# RocMan.net
KiCad netlist of a schematic drawn in EAGLE
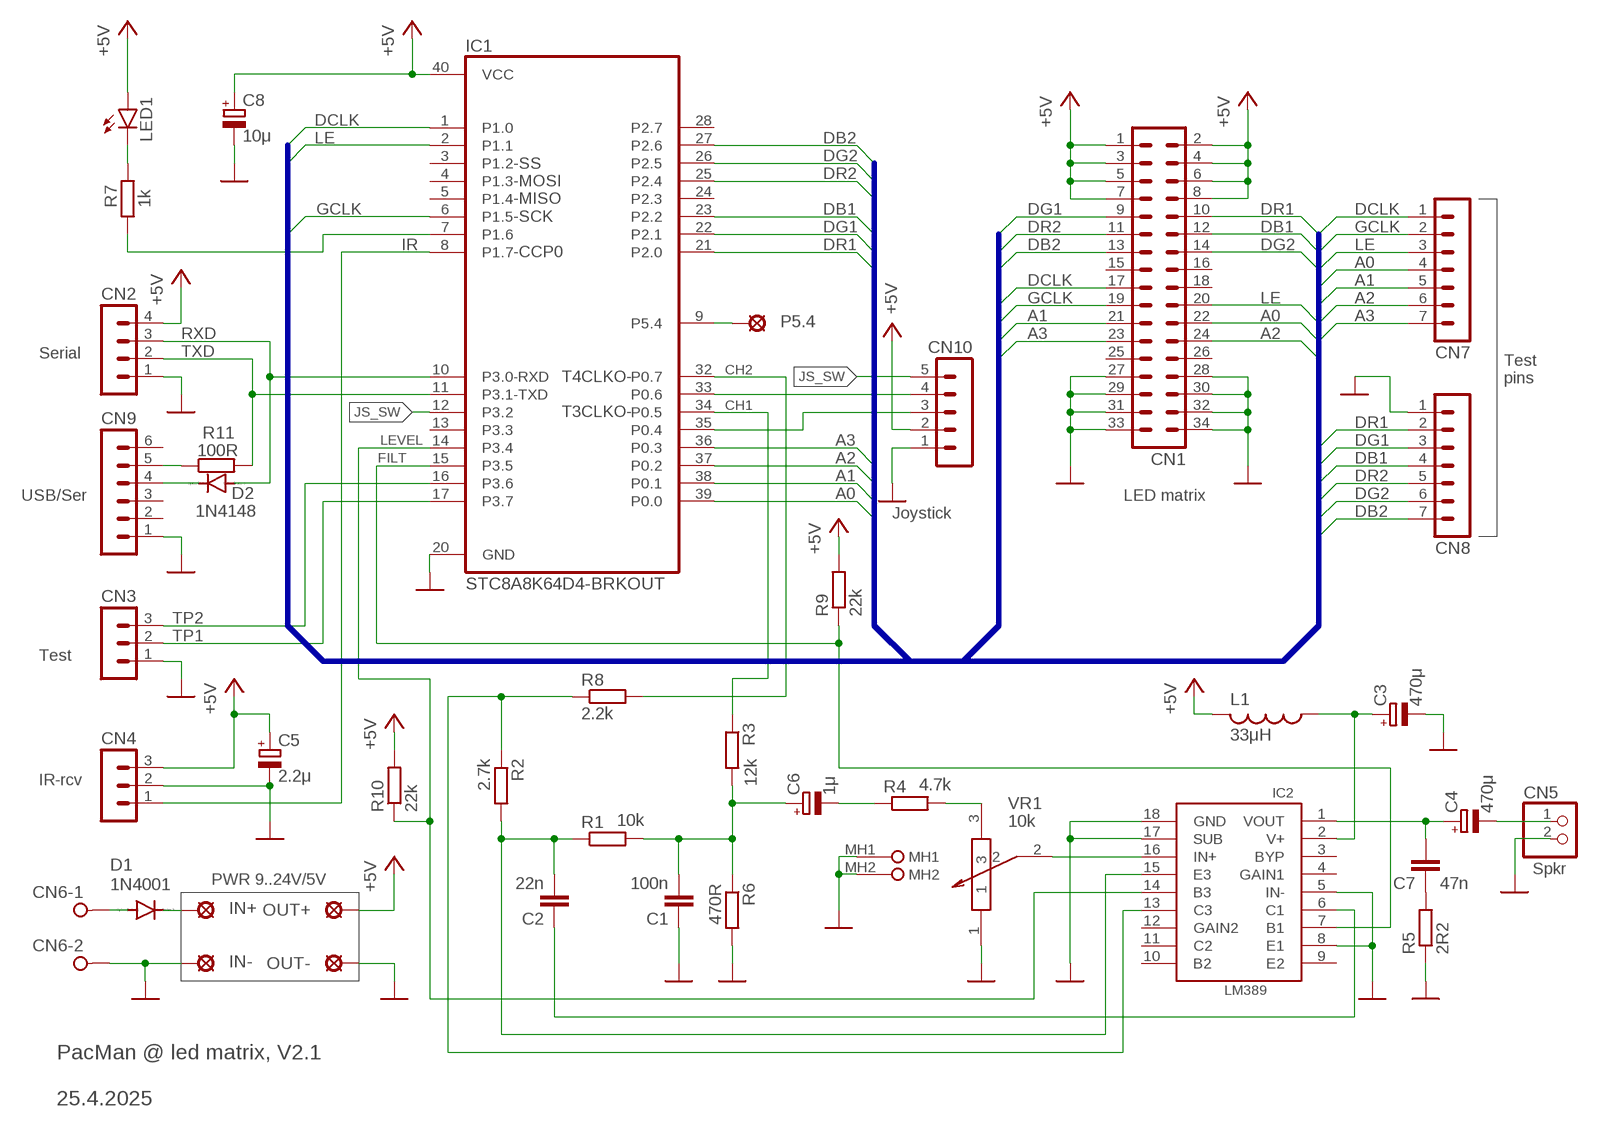
[diagram p0: schematic, sheet 1]

(export (version "E")
  (design (tool "Eeschema 10.0.6"))
  (components
    (comp (ref "C1")
      (value "100n")
      (footprint "eagle-import:C0805")
      (libsource (lib "eagle-import") (part "C-EUC0805"))
    )
    (comp (ref "C2")
      (value "22n")
      (footprint "eagle-import:C0805")
      (libsource (lib "eagle-import") (part "C-EUC0805"))
    )
    (comp (ref "C3")
      (value "470μ")
      (footprint "eagle-import:E5-10,5")
      (libsource (lib "eagle-import") (part "CPOL-EUE5-10.5"))
    )
    (comp (ref "C4")
      (value "470μ")
      (footprint "eagle-import:E5-10,5")
      (libsource (lib "eagle-import") (part "CPOL-EUE5-10.5"))
    )
    (comp (ref "C5")
      (value "2.2μ")
      (footprint "eagle-import:SMC_A")
      (libsource (lib "eagle-import") (part "CPOL-EUSMCA"))
    )
    (comp (ref "C6")
      (value "1μ")
      (footprint "eagle-import:SMC_A")
      (libsource (lib "eagle-import") (part "CPOL-EUSMCA"))
    )
    (comp (ref "C7")
      (value "47n")
      (footprint "eagle-import:C0805")
      (libsource (lib "eagle-import") (part "C-EUC0805"))
    )
    (comp (ref "C8")
      (value "10μ")
      (footprint "eagle-import:SMC_A")
      (libsource (lib "eagle-import") (part "CPOL-EUSMCA"))
    )
    (comp (ref "CN1")
      (value "ML34")
      (footprint "eagle-import:ML34")
      (libsource (lib "eagle-import") (part "ML34"))
    )
    (comp (ref "CN2")
      (value "MA04-1")
      (footprint "eagle-import:MA04-1")
      (libsource (lib "eagle-import") (part "MA04-1"))
    )
    (comp (ref "CN3")
      (value "MA03-1")
      (footprint "eagle-import:MA03-1")
      (libsource (lib "eagle-import") (part "MA03-1"))
    )
    (comp (ref "CN4")
      (value "MA03-1")
      (footprint "eagle-import:MA03-1")
      (libsource (lib "eagle-import") (part "MA03-1"))
    )
    (comp (ref "CN5")
      (value "PINHD-1X2")
      (footprint "eagle-import:1X02")
      (libsource (lib "eagle-import") (part "PINHD-1X2"))
    )
    (comp (ref "CN6")
      (value "W237-02P")
      (footprint "eagle-import:W237-132")
      (libsource (lib "eagle-import") (part "W237-02P"))
    )
    (comp (ref "CN7")
      (value "MA07-1")
      (footprint "eagle-import:MA07-1")
      (libsource (lib "eagle-import") (part "MA07-1"))
    )
    (comp (ref "CN8")
      (value "MA07-1")
      (footprint "eagle-import:MA07-1")
      (libsource (lib "eagle-import") (part "MA07-1"))
    )
    (comp (ref "CN9")
      (value "MA06-1")
      (footprint "eagle-import:MA06-1")
      (libsource (lib "eagle-import") (part "MA06-1"))
    )
    (comp (ref "CN10")
      (value "MA05-1")
      (footprint "eagle-import:MA05-1")
      (libsource (lib "eagle-import") (part "MA05-1"))
    )
    (comp (ref "D1")
      (value "1N4001")
      (footprint "eagle-import:DO41-10")
      (libsource (lib "eagle-import") (part "1N4004"))
    )
    (comp (ref "D2")
      (value "1N4148")
      (footprint "eagle-import:SOD123")
      (libsource (lib "eagle-import") (part "DIODE-SOD123"))
    )
    (comp (ref "IC1")
      (value "STC8A8K64D4-BRKOUT")
      (footprint "eagle-import:DIL40")
      (libsource (lib "eagle-import") (part "STC8A8K64D4-BRKOUT"))
    )
    (comp (ref "IC2")
      (value "LM389")
      (footprint "eagle-import:DIL18")
      (libsource (lib "eagle-import") (part "LM389"))
    )
    (comp (ref "IN+")
      (value "LSP11")
      (footprint "eagle-import:LSP11")
      (libsource (lib "eagle-import") (part "LSP11"))
    )
    (comp (ref "IN-")
      (value "LSP11")
      (footprint "eagle-import:LSP11")
      (libsource (lib "eagle-import") (part "LSP11"))
    )
    (comp (ref "L1")
      (value "33μH")
      (footprint "eagle-import:L4532M")
      (libsource (lib "eagle-import") (part "L-USL4532C"))
    )
    (comp (ref "LED1")
      (value "LEDCHIP-LED0805")
      (footprint "eagle-import:CHIP-LED0805")
      (libsource (lib "eagle-import") (part "LEDCHIP-LED0805"))
    )
    (comp (ref "OUT+")
      (value "LSP11")
      (footprint "eagle-import:LSP11")
      (libsource (lib "eagle-import") (part "LSP11"))
    )
    (comp (ref "OUT-")
      (value "LSP11")
      (footprint "eagle-import:LSP11")
      (libsource (lib "eagle-import") (part "LSP11"))
    )
    (comp (ref "P5.4")
      (value "LSP11")
      (footprint "eagle-import:LSP11")
      (libsource (lib "eagle-import") (part "LSP11"))
    )
    (comp (ref "R1")
      (value "10k")
      (footprint "eagle-import:R0805")
      (libsource (lib "eagle-import") (part "R-EU_R0805"))
    )
    (comp (ref "R2")
      (value "2.7k")
      (footprint "eagle-import:R0805")
      (libsource (lib "eagle-import") (part "R-EU_R0805"))
    )
    (comp (ref "R3")
      (value "12k")
      (footprint "eagle-import:R0805")
      (libsource (lib "eagle-import") (part "R-EU_R0805"))
    )
    (comp (ref "R4")
      (value "4.7k")
      (footprint "eagle-import:R0805")
      (libsource (lib "eagle-import") (part "R-EU_R0805"))
    )
    (comp (ref "R5")
      (value "2R2")
      (footprint "eagle-import:R0805")
      (libsource (lib "eagle-import") (part "R-EU_R0805"))
    )
    (comp (ref "R6")
      (value "470R")
      (footprint "eagle-import:R0805")
      (libsource (lib "eagle-import") (part "R-EU_R0805"))
    )
    (comp (ref "R7")
      (value "1k")
      (footprint "eagle-import:R0805")
      (libsource (lib "eagle-import") (part "R-EU_R0805"))
    )
    (comp (ref "R8")
      (value "2.2k")
      (footprint "eagle-import:R0805")
      (libsource (lib "eagle-import") (part "R-EU_R0805"))
    )
    (comp (ref "R9")
      (value "22k")
      (footprint "eagle-import:R0805")
      (libsource (lib "eagle-import") (part "R-EU_R0805"))
    )
    (comp (ref "R10")
      (value "22k")
      (footprint "eagle-import:R0805")
      (libsource (lib "eagle-import") (part "R-EU_R0805"))
    )
    (comp (ref "R11")
      (value "100R")
      (footprint "eagle-import:R0805")
      (libsource (lib "eagle-import") (part "R-EU_R0805"))
    )
    (comp (ref "VR1")
      (value "10k")
      (footprint "eagle-import:PTV09A4015FA103")
      (fields
        (field (name "MANUFACTURER_PART_NUMBER") "PTV09A-4015F-A103")
        (field (name "MOUSER_PART_NUMBER") "652-PTV09A-4015FA103")
      )
      (libsource (lib "eagle-import") (part "PTV09A-4015F-A103"))
    )
  )
  (nets
    (net (code "1") (name "+5V") (class "Default")
      (node (ref "C5") (pin "+") (pinfunction "+_+") (pintype "passive"))
      (node (ref "C8") (pin "+") (pinfunction "+_+") (pintype "passive"))
      (node (ref "CN1") (pin "1") (pinfunction "1_1") (pintype "passive"))
      (node (ref "CN1") (pin "2") (pinfunction "2_2") (pintype "passive"))
      (node (ref "CN1") (pin "3") (pinfunction "3_3") (pintype "passive"))
      (node (ref "CN1") (pin "4") (pinfunction "4_4") (pintype "passive"))
      (node (ref "CN1") (pin "5") (pinfunction "5_5") (pintype "passive"))
      (node (ref "CN1") (pin "6") (pinfunction "6_6") (pintype "passive"))
      (node (ref "CN1") (pin "7") (pinfunction "7_7") (pintype "passive"))
      (node (ref "CN1") (pin "8") (pinfunction "8_8") (pintype "passive"))
      (node (ref "CN10") (pin "2") (pinfunction "2_2") (pintype "passive"))
      (node (ref "CN2") (pin "4") (pinfunction "4_4") (pintype "passive"))
      (node (ref "CN4") (pin "3") (pinfunction "3_3") (pintype "passive"))
      (node (ref "IC1") (pin "40") (pinfunction "VCC_40") (pintype "power_in"))
      (node (ref "L1") (pin "2") (pinfunction "2_2") (pintype "passive"))
      (node (ref "LED1") (pin "A") (pinfunction "A_A") (pintype "passive"))
      (node (ref "OUT+") (pin "MP") (pinfunction "MP_MP") (pintype "passive"))
      (node (ref "R10") (pin "2") (pinfunction "2_2") (pintype "passive"))
      (node (ref "R9") (pin "2") (pinfunction "2_2") (pintype "passive"))
    )
    (net (code "2") (name "/A0") (class "Default")
      (node (ref "CN1") (pin "22") (pinfunction "22_22") (pintype "passive"))
      (node (ref "CN7") (pin "4") (pinfunction "4_4") (pintype "passive"))
      (node (ref "IC1") (pin "39") (pinfunction "P0.0_39") (pintype "bidirectional"))
    )
    (net (code "3") (name "/A1") (class "Default")
      (node (ref "CN1") (pin "21") (pinfunction "21_21") (pintype "passive"))
      (node (ref "CN7") (pin "5") (pinfunction "5_5") (pintype "passive"))
      (node (ref "IC1") (pin "38") (pinfunction "P0.1_38") (pintype "bidirectional"))
    )
    (net (code "4") (name "/A2") (class "Default")
      (node (ref "CN1") (pin "24") (pinfunction "24_24") (pintype "passive"))
      (node (ref "CN7") (pin "6") (pinfunction "6_6") (pintype "passive"))
      (node (ref "IC1") (pin "37") (pinfunction "P0.2_37") (pintype "bidirectional"))
    )
    (net (code "5") (name "/A3") (class "Default")
      (node (ref "CN1") (pin "23") (pinfunction "23_23") (pintype "passive"))
      (node (ref "CN7") (pin "7") (pinfunction "7_7") (pintype "passive"))
      (node (ref "IC1") (pin "36") (pinfunction "P0.3_36") (pintype "bidirectional"))
    )
    (net (code "6") (name "/CH1") (class "Default")
      (node (ref "IC1") (pin "34") (pinfunction "P0.5_34") (pintype "bidirectional"))
      (node (ref "R3") (pin "1") (pinfunction "1_1") (pintype "passive"))
    )
    (net (code "7") (name "/CH2") (class "Default")
      (node (ref "IC1") (pin "32") (pinfunction "P0.7_32") (pintype "bidirectional"))
      (node (ref "R8") (pin "2") (pinfunction "2_2") (pintype "passive"))
    )
    (net (code "8") (name "/DB1") (class "Default")
      (node (ref "CN1") (pin "12") (pinfunction "12_12") (pintype "passive"))
      (node (ref "CN8") (pin "4") (pinfunction "4_4") (pintype "passive"))
      (node (ref "IC1") (pin "23") (pinfunction "P2.2_23") (pintype "bidirectional"))
    )
    (net (code "9") (name "/DB2") (class "Default")
      (node (ref "CN1") (pin "13") (pinfunction "13_13") (pintype "passive"))
      (node (ref "CN8") (pin "7") (pinfunction "7_7") (pintype "passive"))
      (node (ref "IC1") (pin "27") (pinfunction "P2.6_27") (pintype "bidirectional"))
    )
    (net (code "10") (name "/DCLK") (class "Default")
      (node (ref "CN1") (pin "17") (pinfunction "17_17") (pintype "passive"))
      (node (ref "CN7") (pin "1") (pinfunction "1_1") (pintype "passive"))
      (node (ref "IC1") (pin "1") (pinfunction "P1.0_1") (pintype "bidirectional"))
    )
    (net (code "11") (name "/DG1") (class "Default")
      (node (ref "CN1") (pin "9") (pinfunction "9_9") (pintype "passive"))
      (node (ref "CN8") (pin "3") (pinfunction "3_3") (pintype "passive"))
      (node (ref "IC1") (pin "22") (pinfunction "P2.1_22") (pintype "bidirectional"))
    )
    (net (code "12") (name "/DG2") (class "Default")
      (node (ref "CN1") (pin "14") (pinfunction "14_14") (pintype "passive"))
      (node (ref "CN8") (pin "6") (pinfunction "6_6") (pintype "passive"))
      (node (ref "IC1") (pin "26") (pinfunction "P2.5_26") (pintype "bidirectional"))
    )
    (net (code "13") (name "/DR1") (class "Default")
      (node (ref "CN1") (pin "10") (pinfunction "10_10") (pintype "passive"))
      (node (ref "CN8") (pin "2") (pinfunction "2_2") (pintype "passive"))
      (node (ref "IC1") (pin "21") (pinfunction "P2.0_21") (pintype "bidirectional"))
    )
    (net (code "14") (name "/DR2") (class "Default")
      (node (ref "CN1") (pin "11") (pinfunction "11_11") (pintype "passive"))
      (node (ref "CN8") (pin "5") (pinfunction "5_5") (pintype "passive"))
      (node (ref "IC1") (pin "25") (pinfunction "P2.4_25") (pintype "bidirectional"))
    )
    (net (code "15") (name "/FILT") (class "Default")
      (node (ref "IC1") (pin "15") (pinfunction "P3.5_15") (pintype "bidirectional"))
      (node (ref "IC2") (pin "7") (pinfunction "B1_7") (pintype "bidirectional"))
      (node (ref "R9") (pin "1") (pinfunction "1_1") (pintype "passive"))
    )
    (net (code "16") (name "/GCLK") (class "Default")
      (node (ref "CN1") (pin "19") (pinfunction "19_19") (pintype "passive"))
      (node (ref "CN7") (pin "2") (pinfunction "2_2") (pintype "passive"))
      (node (ref "IC1") (pin "6") (pinfunction "P1.5_6") (pintype "bidirectional"))
    )
    (net (code "17") (name "/IR") (class "Default")
      (node (ref "CN4") (pin "1") (pinfunction "1_1") (pintype "passive"))
      (node (ref "IC1") (pin "8") (pinfunction "P1.7_8") (pintype "bidirectional"))
    )
    (net (code "18") (name "/LE") (class "Default")
      (node (ref "CN1") (pin "20") (pinfunction "20_20") (pintype "passive"))
      (node (ref "CN7") (pin "3") (pinfunction "3_3") (pintype "passive"))
      (node (ref "IC1") (pin "2") (pinfunction "P1.1_2") (pintype "bidirectional"))
    )
    (net (code "19") (name "/LEVEL") (class "Default")
      (node (ref "IC1") (pin "14") (pinfunction "P3.4_14") (pintype "bidirectional"))
      (node (ref "IC2") (pin "14") (pinfunction "B3_14") (pintype "bidirectional"))
      (node (ref "R10") (pin "1") (pinfunction "1_1") (pintype "passive"))
    )
    (net (code "20") (name "/RXD") (class "Default")
      (node (ref "CN2") (pin "3") (pinfunction "3_3") (pintype "passive"))
      (node (ref "D2") (pin "A") (pinfunction "A_A") (pintype "passive"))
      (node (ref "IC1") (pin "10") (pinfunction "P3.0-RXD_10") (pintype "bidirectional"))
    )
    (net (code "21") (name "/TP1") (class "Default")
      (node (ref "CN3") (pin "2") (pinfunction "2_2") (pintype "passive"))
      (node (ref "IC1") (pin "17") (pinfunction "P3.7_17") (pintype "bidirectional"))
    )
    (net (code "22") (name "/TP2") (class "Default")
      (node (ref "CN3") (pin "3") (pinfunction "3_3") (pintype "passive"))
      (node (ref "IC1") (pin "16") (pinfunction "P3.6_16") (pintype "bidirectional"))
    )
    (net (code "23") (name "/TXD") (class "Default")
      (node (ref "CN2") (pin "2") (pinfunction "2_2") (pintype "passive"))
      (node (ref "IC1") (pin "11") (pinfunction "P3.1-TXD_11") (pintype "bidirectional"))
      (node (ref "R11") (pin "2") (pinfunction "2_2") (pintype "passive"))
    )
    (net (code "24") (name "GND") (class "Default")
      (node (ref "C1") (pin "1") (pinfunction "1_1") (pintype "passive"))
      (node (ref "C3") (pin "-") (pinfunction "-_-") (pintype "passive"))
      (node (ref "C5") (pin "-") (pinfunction "-_-") (pintype "passive"))
      (node (ref "C8") (pin "-") (pinfunction "-_-") (pintype "passive"))
      (node (ref "CN1") (pin "27") (pinfunction "27_27") (pintype "passive"))
      (node (ref "CN1") (pin "28") (pinfunction "28_28") (pintype "passive"))
      (node (ref "CN1") (pin "29") (pinfunction "29_29") (pintype "passive"))
      (node (ref "CN1") (pin "30") (pinfunction "30_30") (pintype "passive"))
      (node (ref "CN1") (pin "31") (pinfunction "31_31") (pintype "passive"))
      (node (ref "CN1") (pin "32") (pinfunction "32_32") (pintype "passive"))
      (node (ref "CN1") (pin "33") (pinfunction "33_33") (pintype "passive"))
      (node (ref "CN1") (pin "34") (pinfunction "34_34") (pintype "passive"))
      (node (ref "CN10") (pin "1") (pinfunction "1_1") (pintype "passive"))
      (node (ref "CN2") (pin "1") (pinfunction "1_1") (pintype "passive"))
      (node (ref "CN3") (pin "1") (pinfunction "1_1") (pintype "passive"))
      (node (ref "CN4") (pin "2") (pinfunction "2_2") (pintype "passive"))
      (node (ref "CN5") (pin "2") (pinfunction "2_2") (pintype "passive"))
      (node (ref "CN6") (pin "2") (pinfunction "KL_2") (pintype "passive"))
      (node (ref "CN8") (pin "1") (pinfunction "1_1") (pintype "passive"))
      (node (ref "CN9") (pin "1") (pinfunction "1_1") (pintype "passive"))
      (node (ref "IC1") (pin "20") (pinfunction "GND_20") (pintype "power_in"))
      (node (ref "IC2") (pin "17") (pinfunction "SUB_17") (pintype "power_in"))
      (node (ref "IC2") (pin "18") (pinfunction "GND_18") (pintype "power_in"))
      (node (ref "IC2") (pin "5") (pinfunction "IN-_5") (pintype "bidirectional"))
      (node (ref "IC2") (pin "8") (pinfunction "E1_8") (pintype "bidirectional"))
      (node (ref "IN-") (pin "MP") (pinfunction "MP_MP") (pintype "passive"))
      (node (ref "OUT-") (pin "MP") (pinfunction "MP_MP") (pintype "passive"))
      (node (ref "R5") (pin "1") (pinfunction "1_1") (pintype "passive"))
      (node (ref "R6") (pin "2") (pinfunction "2_2") (pintype "passive"))
      (node (ref "VR1") (pin "1") (pinfunction "1_1") (pintype "bidirectional"))
      (node (ref "VR1") (pin "MH1") (pinfunction "MH1_MH1") (pintype "bidirectional"))
      (node (ref "VR1") (pin "MH2") (pinfunction "MH2_MH2") (pintype "bidirectional"))
    )
    (net (code "25") (name "JS_SW") (class "Default")
      (node (ref "CN10") (pin "5") (pinfunction "5_5") (pintype "passive"))
      (node (ref "IC1") (pin "12") (pinfunction "P3.2_12") (pintype "bidirectional"))
    )
    (net (code "26") (name "Net-(C1-Pad2)") (class "Default")
      (node (ref "C1") (pin "2") (pinfunction "2_2") (pintype "passive"))
      (node (ref "C6") (pin "+") (pinfunction "+_+") (pintype "passive"))
      (node (ref "R1") (pin "2") (pinfunction "2_2") (pintype "passive"))
      (node (ref "R3") (pin "2") (pinfunction "2_2") (pintype "passive"))
      (node (ref "R6") (pin "1") (pinfunction "1_1") (pintype "passive"))
    )
    (net (code "27") (name "Net-(C4-Pad-)") (class "Default")
      (node (ref "C4") (pin "-") (pinfunction "-_-") (pintype "passive"))
      (node (ref "CN5") (pin "1") (pinfunction "1_1") (pintype "passive"))
    )
    (net (code "28") (name "Net-(C6-Pad-)") (class "Default")
      (node (ref "C6") (pin "-") (pinfunction "-_-") (pintype "passive"))
      (node (ref "R4") (pin "1") (pinfunction "1_1") (pintype "passive"))
    )
    (net (code "29") (name "Net-(C7-Pad1)") (class "Default")
      (node (ref "C7") (pin "1") (pinfunction "1_1") (pintype "passive"))
      (node (ref "R5") (pin "2") (pinfunction "2_2") (pintype "passive"))
    )
    (net (code "30") (name "Net-(CN6A-KL)") (class "Default")
      (node (ref "CN6") (pin "1") (pinfunction "KL_1") (pintype "passive"))
      (node (ref "D1") (pin "A") (pinfunction "A_A") (pintype "passive"))
    )
    (net (code "31") (name "Net-(CN9-Pad4)") (class "Default")
      (node (ref "CN9") (pin "4") (pinfunction "4_4") (pintype "passive"))
      (node (ref "D2") (pin "C") (pinfunction "C_C") (pintype "passive"))
    )
    (net (code "32") (name "Net-(CN9-Pad5)") (class "Default")
      (node (ref "CN9") (pin "5") (pinfunction "5_5") (pintype "passive"))
      (node (ref "R11") (pin "1") (pinfunction "1_1") (pintype "passive"))
    )
    (net (code "33") (name "Net-(D1-PadC)") (class "Default")
      (node (ref "D1") (pin "C") (pinfunction "C_C") (pintype "passive"))
      (node (ref "IN+") (pin "MP") (pinfunction "MP_MP") (pintype "passive"))
    )
    (net (code "34") (name "Net-(IC1-P0.4)") (class "Default")
      (node (ref "CN10") (pin "3") (pinfunction "3_3") (pintype "passive"))
      (node (ref "IC1") (pin "35") (pinfunction "P0.4_35") (pintype "bidirectional"))
    )
    (net (code "35") (name "Net-(IC1-P0.6)") (class "Default")
      (node (ref "CN10") (pin "4") (pinfunction "4_4") (pintype "passive"))
      (node (ref "IC1") (pin "33") (pinfunction "P0.6_33") (pintype "bidirectional"))
    )
    (net (code "36") (name "Net-(IC1-P1.6)") (class "Default")
      (node (ref "IC1") (pin "7") (pinfunction "P1.6_7") (pintype "bidirectional"))
      (node (ref "R7") (pin "1") (pinfunction "1_1") (pintype "passive"))
    )
    (net (code "37") (name "Net-(IC1-P5.4)") (class "Default")
      (node (ref "IC1") (pin "9") (pinfunction "P5.4_9") (pintype "input"))
      (node (ref "P5.4") (pin "MP") (pinfunction "MP_MP") (pintype "passive"))
    )
    (net (code "38") (name "Net-(IC2-C1)") (class "Default")
      (node (ref "C2") (pin "1") (pinfunction "1_1") (pintype "passive"))
      (node (ref "IC2") (pin "6") (pinfunction "C1_6") (pintype "bidirectional"))
    )
    (net (code "39") (name "Net-(IC2-C3)") (class "Default")
      (node (ref "IC2") (pin "13") (pinfunction "C3_13") (pintype "bidirectional"))
      (node (ref "R2") (pin "1") (pinfunction "1_1") (pintype "passive"))
      (node (ref "R8") (pin "1") (pinfunction "1_1") (pintype "passive"))
    )
    (net (code "40") (name "Net-(IC2-E3)") (class "Default")
      (node (ref "C2") (pin "2") (pinfunction "2_2") (pintype "passive"))
      (node (ref "IC2") (pin "15") (pinfunction "E3_15") (pintype "bidirectional"))
      (node (ref "R1") (pin "1") (pinfunction "1_1") (pintype "passive"))
      (node (ref "R2") (pin "2") (pinfunction "2_2") (pintype "passive"))
    )
    (net (code "41") (name "Net-(IC2-IN+)") (class "Default")
      (node (ref "IC2") (pin "16") (pinfunction "IN+_16") (pintype "bidirectional"))
      (node (ref "VR1") (pin "2") (pinfunction "2_2") (pintype "bidirectional"))
    )
    (net (code "42") (name "Net-(IC2-V+)") (class "Default")
      (node (ref "C3") (pin "+") (pinfunction "+_+") (pintype "passive"))
      (node (ref "IC2") (pin "2") (pinfunction "V+_2") (pintype "power_in"))
      (node (ref "L1") (pin "1") (pinfunction "1_1") (pintype "passive"))
    )
    (net (code "43") (name "Net-(IC2-VOUT)") (class "Default")
      (node (ref "C4") (pin "+") (pinfunction "+_+") (pintype "passive"))
      (node (ref "C7") (pin "2") (pinfunction "2_2") (pintype "passive"))
      (node (ref "IC2") (pin "1") (pinfunction "VOUT_1") (pintype "bidirectional"))
    )
    (net (code "44") (name "Net-(LED1-PadC)") (class "Default")
      (node (ref "LED1") (pin "C") (pinfunction "C_C") (pintype "passive"))
      (node (ref "R7") (pin "2") (pinfunction "2_2") (pintype "passive"))
    )
    (net (code "45") (name "Net-(R4-Pad2)") (class "Default")
      (node (ref "R4") (pin "2") (pinfunction "2_2") (pintype "passive"))
      (node (ref "VR1") (pin "3") (pinfunction "3_3") (pintype "bidirectional"))
    )
    (net (code "46") (name "unconnected-(CN1-Pad15)") (class "Default")
      (node (ref "CN1") (pin "15") (pinfunction "15_15") (pintype "passive"))
    )
    (net (code "47") (name "unconnected-(CN1-Pad16)") (class "Default")
      (node (ref "CN1") (pin "16") (pinfunction "16_16") (pintype "passive"))
    )
    (net (code "48") (name "unconnected-(CN1-Pad18)") (class "Default")
      (node (ref "CN1") (pin "18") (pinfunction "18_18") (pintype "passive"))
    )
    (net (code "49") (name "unconnected-(CN1-Pad25)") (class "Default")
      (node (ref "CN1") (pin "25") (pinfunction "25_25") (pintype "passive"))
    )
    (net (code "50") (name "unconnected-(CN1-Pad26)") (class "Default")
      (node (ref "CN1") (pin "26") (pinfunction "26_26") (pintype "passive"))
    )
    (net (code "51") (name "unconnected-(CN9-Pad2)") (class "Default")
      (node (ref "CN9") (pin "2") (pinfunction "2_2") (pintype "passive"))
    )
    (net (code "52") (name "unconnected-(CN9-Pad3)") (class "Default")
      (node (ref "CN9") (pin "3") (pinfunction "3_3") (pintype "passive"))
    )
    (net (code "53") (name "unconnected-(CN9-Pad6)") (class "Default")
      (node (ref "CN9") (pin "6") (pinfunction "6_6") (pintype "passive"))
    )
    (net (code "54") (name "unconnected-(IC1-P1.2-Pad3)") (class "Default")
      (node (ref "IC1") (pin "3") (pinfunction "P1.2_3") (pintype "bidirectional"))
    )
    (net (code "55") (name "unconnected-(IC1-P1.3-Pad4)") (class "Default")
      (node (ref "IC1") (pin "4") (pinfunction "P1.3_4") (pintype "bidirectional"))
    )
    (net (code "56") (name "unconnected-(IC1-P1.4-Pad5)") (class "Default")
      (node (ref "IC1") (pin "5") (pinfunction "P1.4_5") (pintype "bidirectional"))
    )
    (net (code "57") (name "unconnected-(IC1-P2.3-Pad24)") (class "Default")
      (node (ref "IC1") (pin "24") (pinfunction "P2.3_24") (pintype "bidirectional"))
    )
    (net (code "58") (name "unconnected-(IC1-P2.7-Pad28)") (class "Default")
      (node (ref "IC1") (pin "28") (pinfunction "P2.7_28") (pintype "bidirectional"))
    )
    (net (code "59") (name "unconnected-(IC1-P3.3-Pad13)") (class "Default")
      (node (ref "IC1") (pin "13") (pinfunction "P3.3_13") (pintype "bidirectional"))
    )
    (net (code "60") (name "unconnected-(IC2-B2-Pad10)") (class "Default")
      (node (ref "IC2") (pin "10") (pinfunction "B2_10") (pintype "bidirectional"))
    )
    (net (code "61") (name "unconnected-(IC2-BYP-Pad3)") (class "Default")
      (node (ref "IC2") (pin "3") (pinfunction "BYP_3") (pintype "bidirectional"))
    )
    (net (code "62") (name "unconnected-(IC2-C2-Pad11)") (class "Default")
      (node (ref "IC2") (pin "11") (pinfunction "C2_11") (pintype "bidirectional"))
    )
    (net (code "63") (name "unconnected-(IC2-E2-Pad9)") (class "Default")
      (node (ref "IC2") (pin "9") (pinfunction "E2_9") (pintype "bidirectional"))
    )
    (net (code "64") (name "unconnected-(IC2-GAIN1-Pad4)") (class "Default")
      (node (ref "IC2") (pin "4") (pinfunction "GAIN1_4") (pintype "bidirectional"))
    )
    (net (code "65") (name "unconnected-(IC2-GAIN2-Pad12)") (class "Default")
      (node (ref "IC2") (pin "12") (pinfunction "GAIN2_12") (pintype "bidirectional"))
    )
  )
)
